# PowerRouting.net
KiCad netlist of a schematic drawn in Altium Designer
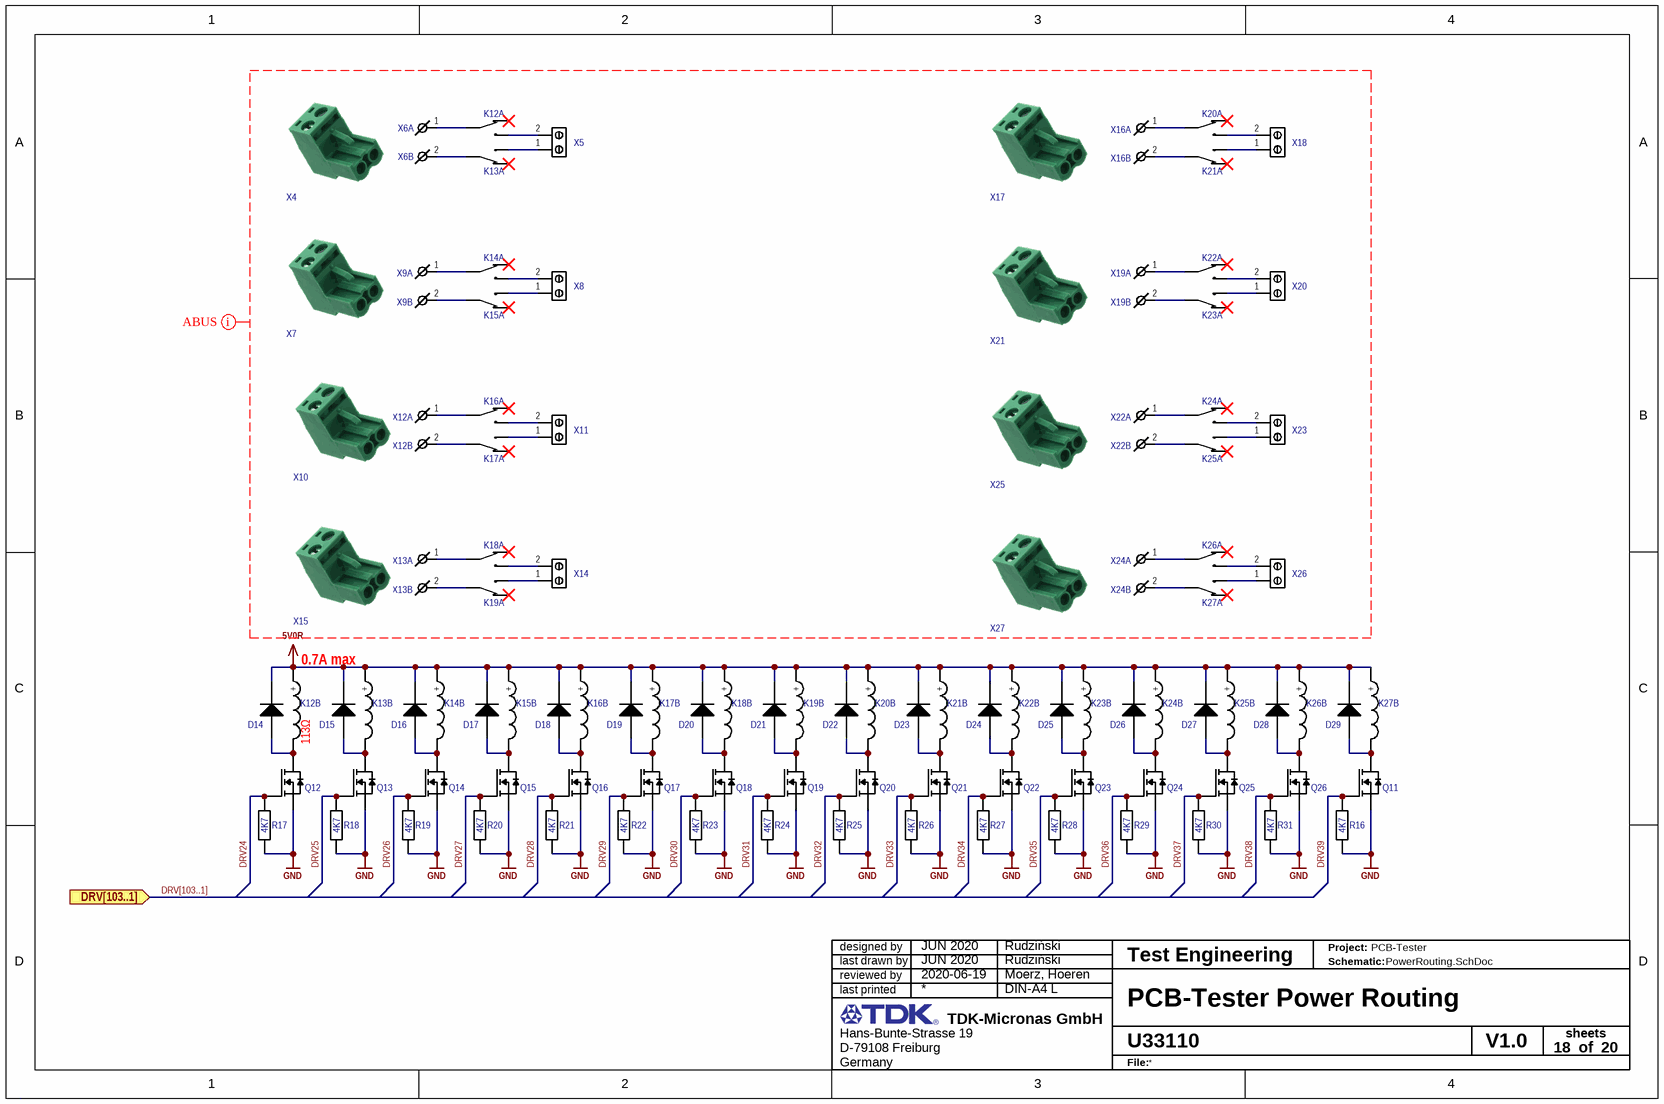
[diagram p0: PowerRouting.SchDoc]

(export (version "E")
  (design (tool "Eeschema 10.0.6"))
  (components
    (comp (ref "D14")
      (value "D")
      (footprint "SOD123")
      (description "DIODE GEN PURP 100V 300MA SOD123")
      (fields
        (field (name "02. DISTRIBUTOR PART NUMBER") "1N4148W-FDICT-ND")
        (field (name "07. MANUFACTURER  PART NUMBER") "1N4148W-7-F")
      )
      (libsource (lib "PCB-Tester-Board-V1") (part "1N4148W"))
    )
    (comp (ref "D15")
      (value "D")
      (footprint "SOD123")
      (description "DIODE GEN PURP 100V 300MA SOD123")
      (fields
        (field (name "02. DISTRIBUTOR PART NUMBER") "1N4148W-FDICT-ND")
        (field (name "07. MANUFACTURER  PART NUMBER") "1N4148W-7-F")
      )
      (libsource (lib "PCB-Tester-Board-V1") (part "1N4148W"))
    )
    (comp (ref "D16")
      (value "D")
      (footprint "SOD123")
      (description "DIODE GEN PURP 100V 300MA SOD123")
      (fields
        (field (name "02. DISTRIBUTOR PART NUMBER") "1N4148W-FDICT-ND")
        (field (name "07. MANUFACTURER  PART NUMBER") "1N4148W-7-F")
      )
      (libsource (lib "PCB-Tester-Board-V1") (part "1N4148W"))
    )
    (comp (ref "D17")
      (value "D")
      (footprint "SOD123")
      (description "DIODE GEN PURP 100V 300MA SOD123")
      (fields
        (field (name "02. DISTRIBUTOR PART NUMBER") "1N4148W-FDICT-ND")
        (field (name "07. MANUFACTURER  PART NUMBER") "1N4148W-7-F")
      )
      (libsource (lib "PCB-Tester-Board-V1") (part "1N4148W"))
    )
    (comp (ref "D18")
      (value "D")
      (footprint "SOD123")
      (description "DIODE GEN PURP 100V 300MA SOD123")
      (fields
        (field (name "02. DISTRIBUTOR PART NUMBER") "1N4148W-FDICT-ND")
        (field (name "07. MANUFACTURER  PART NUMBER") "1N4148W-7-F")
      )
      (libsource (lib "PCB-Tester-Board-V1") (part "1N4148W"))
    )
    (comp (ref "D19")
      (value "D")
      (footprint "SOD123")
      (description "DIODE GEN PURP 100V 300MA SOD123")
      (fields
        (field (name "02. DISTRIBUTOR PART NUMBER") "1N4148W-FDICT-ND")
        (field (name "07. MANUFACTURER  PART NUMBER") "1N4148W-7-F")
      )
      (libsource (lib "PCB-Tester-Board-V1") (part "1N4148W"))
    )
    (comp (ref "D20")
      (value "D")
      (footprint "SOD123")
      (description "DIODE GEN PURP 100V 300MA SOD123")
      (fields
        (field (name "02. DISTRIBUTOR PART NUMBER") "1N4148W-FDICT-ND")
        (field (name "07. MANUFACTURER  PART NUMBER") "1N4148W-7-F")
      )
      (libsource (lib "PCB-Tester-Board-V1") (part "1N4148W"))
    )
    (comp (ref "D21")
      (value "D")
      (footprint "SOD123")
      (description "DIODE GEN PURP 100V 300MA SOD123")
      (fields
        (field (name "02. DISTRIBUTOR PART NUMBER") "1N4148W-FDICT-ND")
        (field (name "07. MANUFACTURER  PART NUMBER") "1N4148W-7-F")
      )
      (libsource (lib "PCB-Tester-Board-V1") (part "1N4148W"))
    )
    (comp (ref "D22")
      (value "D")
      (footprint "SOD123")
      (description "DIODE GEN PURP 100V 300MA SOD123")
      (fields
        (field (name "02. DISTRIBUTOR PART NUMBER") "1N4148W-FDICT-ND")
        (field (name "07. MANUFACTURER  PART NUMBER") "1N4148W-7-F")
      )
      (libsource (lib "PCB-Tester-Board-V1") (part "1N4148W"))
    )
    (comp (ref "D23")
      (value "D")
      (footprint "SOD123")
      (description "DIODE GEN PURP 100V 300MA SOD123")
      (fields
        (field (name "02. DISTRIBUTOR PART NUMBER") "1N4148W-FDICT-ND")
        (field (name "07. MANUFACTURER  PART NUMBER") "1N4148W-7-F")
      )
      (libsource (lib "PCB-Tester-Board-V1") (part "1N4148W"))
    )
    (comp (ref "D24")
      (value "D")
      (footprint "SOD123")
      (description "DIODE GEN PURP 100V 300MA SOD123")
      (fields
        (field (name "02. DISTRIBUTOR PART NUMBER") "1N4148W-FDICT-ND")
        (field (name "07. MANUFACTURER  PART NUMBER") "1N4148W-7-F")
      )
      (libsource (lib "PCB-Tester-Board-V1") (part "1N4148W"))
    )
    (comp (ref "D25")
      (value "D")
      (footprint "SOD123")
      (description "DIODE GEN PURP 100V 300MA SOD123")
      (fields
        (field (name "02. DISTRIBUTOR PART NUMBER") "1N4148W-FDICT-ND")
        (field (name "07. MANUFACTURER  PART NUMBER") "1N4148W-7-F")
      )
      (libsource (lib "PCB-Tester-Board-V1") (part "1N4148W"))
    )
    (comp (ref "D26")
      (value "D")
      (footprint "SOD123")
      (description "DIODE GEN PURP 100V 300MA SOD123")
      (fields
        (field (name "02. DISTRIBUTOR PART NUMBER") "1N4148W-FDICT-ND")
        (field (name "07. MANUFACTURER  PART NUMBER") "1N4148W-7-F")
      )
      (libsource (lib "PCB-Tester-Board-V1") (part "1N4148W"))
    )
    (comp (ref "D27")
      (value "D")
      (footprint "SOD123")
      (description "DIODE GEN PURP 100V 300MA SOD123")
      (fields
        (field (name "02. DISTRIBUTOR PART NUMBER") "1N4148W-FDICT-ND")
        (field (name "07. MANUFACTURER  PART NUMBER") "1N4148W-7-F")
      )
      (libsource (lib "PCB-Tester-Board-V1") (part "1N4148W"))
    )
    (comp (ref "D28")
      (value "D")
      (footprint "SOD123")
      (description "DIODE GEN PURP 100V 300MA SOD123")
      (fields
        (field (name "02. DISTRIBUTOR PART NUMBER") "1N4148W-FDICT-ND")
        (field (name "07. MANUFACTURER  PART NUMBER") "1N4148W-7-F")
      )
      (libsource (lib "PCB-Tester-Board-V1") (part "1N4148W"))
    )
    (comp (ref "D29")
      (value "D")
      (footprint "SOD123")
      (description "DIODE GEN PURP 100V 300MA SOD123")
      (fields
        (field (name "02. DISTRIBUTOR PART NUMBER") "1N4148W-FDICT-ND")
        (field (name "07. MANUFACTURER  PART NUMBER") "1N4148W-7-F")
      )
      (libsource (lib "PCB-Tester-Board-V1") (part "1N4148W"))
    )
    (comp (ref "K12")
      (value "K")
      (footprint "HF118F005-1ZS1")
      (description "5V Power Relay, switch over")
      (fields
        (field (name "02. DISTRIBUTOR PART NUMBER") "176-2821")
        (field (name "07. MANUFACTURER  PART NUMBER") "HF118F/005-1ZS1T(136)")
        (field (name "COIL RESISTANCE") "113Ω")
        (field (name "13. CREATED DATE/NAME") "AUG2018/Hören")
      )
      (libsource (lib "chickenfood") (part "HF118F005-1ZS1"))
    )
    (comp (ref "K13")
      (value "K")
      (footprint "HF118F005-1ZS1")
      (description "5V Power Relay, switch over")
      (fields
        (field (name "02. DISTRIBUTOR PART NUMBER") "176-2821")
        (field (name "07. MANUFACTURER  PART NUMBER") "HF118F/005-1ZS1T(136)")
        (field (name "13. CREATED DATE/NAME") "AUG2018/Hören")
      )
      (libsource (lib "chickenfood") (part "HF118F005-1ZS1"))
    )
    (comp (ref "K14")
      (value "K")
      (footprint "HF118F005-1ZS1")
      (description "5V Power Relay, switch over")
      (fields
        (field (name "02. DISTRIBUTOR PART NUMBER") "176-2821")
        (field (name "07. MANUFACTURER  PART NUMBER") "HF118F/005-1ZS1T(136)")
        (field (name "13. CREATED DATE/NAME") "AUG2018/Hören")
      )
      (libsource (lib "chickenfood") (part "HF118F005-1ZS1"))
    )
    (comp (ref "K15")
      (value "K")
      (footprint "HF118F005-1ZS1")
      (description "5V Power Relay, switch over")
      (fields
        (field (name "02. DISTRIBUTOR PART NUMBER") "176-2821")
        (field (name "07. MANUFACTURER  PART NUMBER") "HF118F/005-1ZS1T(136)")
        (field (name "13. CREATED DATE/NAME") "AUG2018/Hören")
      )
      (libsource (lib "chickenfood") (part "HF118F005-1ZS1"))
    )
    (comp (ref "K16")
      (value "K")
      (footprint "HF118F005-1ZS1")
      (description "5V Power Relay, switch over")
      (fields
        (field (name "02. DISTRIBUTOR PART NUMBER") "176-2821")
        (field (name "07. MANUFACTURER  PART NUMBER") "HF118F/005-1ZS1T(136)")
        (field (name "13. CREATED DATE/NAME") "AUG2018/Hören")
      )
      (libsource (lib "chickenfood") (part "HF118F005-1ZS1"))
    )
    (comp (ref "K17")
      (value "K")
      (footprint "HF118F005-1ZS1")
      (description "5V Power Relay, switch over")
      (fields
        (field (name "02. DISTRIBUTOR PART NUMBER") "176-2821")
        (field (name "07. MANUFACTURER  PART NUMBER") "HF118F/005-1ZS1T(136)")
        (field (name "13. CREATED DATE/NAME") "AUG2018/Hören")
      )
      (libsource (lib "") (part "HF118F005-1ZS1_1"))
    )
    (comp (ref "K18")
      (value "K")
      (footprint "HF118F005-1ZS1")
      (description "5V Power Relay, switch over")
      (fields
        (field (name "02. DISTRIBUTOR PART NUMBER") "176-2821")
        (field (name "07. MANUFACTURER  PART NUMBER") "HF118F/005-1ZS1T(136)")
        (field (name "13. CREATED DATE/NAME") "AUG2018/Hören")
      )
      (libsource (lib "chickenfood") (part "HF118F005-1ZS1"))
    )
    (comp (ref "K19")
      (value "K")
      (footprint "HF118F005-1ZS1")
      (description "5V Power Relay, switch over")
      (fields
        (field (name "02. DISTRIBUTOR PART NUMBER") "176-2821")
        (field (name "07. MANUFACTURER  PART NUMBER") "HF118F/005-1ZS1T(136)")
        (field (name "13. CREATED DATE/NAME") "AUG2018/Hören")
      )
      (libsource (lib "") (part "HF118F005-1ZS1_1"))
    )
    (comp (ref "K20")
      (value "K")
      (footprint "HF118F005-1ZS1")
      (description "5V Power Relay, switch over")
      (fields
        (field (name "02. DISTRIBUTOR PART NUMBER") "176-2821")
        (field (name "07. MANUFACTURER  PART NUMBER") "HF118F/005-1ZS1T(136)")
        (field (name "13. CREATED DATE/NAME") "AUG2018/Hören")
      )
      (libsource (lib "chickenfood") (part "HF118F005-1ZS1"))
    )
    (comp (ref "K21")
      (value "K")
      (footprint "HF118F005-1ZS1")
      (description "5V Power Relay, switch over")
      (fields
        (field (name "02. DISTRIBUTOR PART NUMBER") "176-2821")
        (field (name "07. MANUFACTURER  PART NUMBER") "HF118F/005-1ZS1T(136)")
        (field (name "13. CREATED DATE/NAME") "AUG2018/Hören")
      )
      (libsource (lib "chickenfood") (part "HF118F005-1ZS1"))
    )
    (comp (ref "K22")
      (value "K")
      (footprint "HF118F005-1ZS1")
      (description "5V Power Relay, switch over")
      (fields
        (field (name "02. DISTRIBUTOR PART NUMBER") "176-2821")
        (field (name "07. MANUFACTURER  PART NUMBER") "HF118F/005-1ZS1T(136)")
        (field (name "13. CREATED DATE/NAME") "AUG2018/Hören")
      )
      (libsource (lib "chickenfood") (part "HF118F005-1ZS1"))
    )
    (comp (ref "K23")
      (value "K")
      (footprint "HF118F005-1ZS1")
      (description "5V Power Relay, switch over")
      (fields
        (field (name "02. DISTRIBUTOR PART NUMBER") "176-2821")
        (field (name "07. MANUFACTURER  PART NUMBER") "HF118F/005-1ZS1T(136)")
        (field (name "13. CREATED DATE/NAME") "AUG2018/Hören")
      )
      (libsource (lib "") (part "HF118F005-1ZS1_1"))
    )
    (comp (ref "K24")
      (value "K")
      (footprint "HF118F005-1ZS1")
      (description "5V Power Relay, switch over")
      (fields
        (field (name "02. DISTRIBUTOR PART NUMBER") "176-2821")
        (field (name "07. MANUFACTURER  PART NUMBER") "HF118F/005-1ZS1T(136)")
        (field (name "13. CREATED DATE/NAME") "AUG2018/Hören")
      )
      (libsource (lib "chickenfood") (part "HF118F005-1ZS1"))
    )
    (comp (ref "K25")
      (value "K")
      (footprint "HF118F005-1ZS1")
      (description "5V Power Relay, switch over")
      (fields
        (field (name "02. DISTRIBUTOR PART NUMBER") "176-2821")
        (field (name "07. MANUFACTURER  PART NUMBER") "HF118F/005-1ZS1T(136)")
        (field (name "13. CREATED DATE/NAME") "AUG2018/Hören")
      )
      (libsource (lib "") (part "HF118F005-1ZS1_1"))
    )
    (comp (ref "K26")
      (value "K")
      (footprint "HF118F005-1ZS1")
      (description "5V Power Relay, switch over")
      (fields
        (field (name "02. DISTRIBUTOR PART NUMBER") "176-2821")
        (field (name "07. MANUFACTURER  PART NUMBER") "HF118F/005-1ZS1T(136)")
        (field (name "13. CREATED DATE/NAME") "AUG2018/Hören")
      )
      (libsource (lib "chickenfood") (part "HF118F005-1ZS1"))
    )
    (comp (ref "K27")
      (value "K")
      (footprint "HF118F005-1ZS1")
      (description "5V Power Relay, switch over")
      (fields
        (field (name "02. DISTRIBUTOR PART NUMBER") "176-2821")
        (field (name "07. MANUFACTURER  PART NUMBER") "HF118F/005-1ZS1T(136)")
        (field (name "13. CREATED DATE/NAME") "AUG2018/Hören")
      )
      (libsource (lib "") (part "HF118F005-1ZS1_1"))
    )
    (comp (ref "Q11")
      (value "Q")
      (footprint "SOT23-3")
      (description "MOSFET N-CH 25V 680MA SOT-23")
      (fields
        (field (name "02. DISTRIBUTOR PART NUMBER") "FDV303NDKR-ND")
        (field (name "07. MANUFACTURER  PART NUMBER") "FDV303N")
        (field (name "13. CREATED DATE/NAME") "AUG 2018 / Hören")
      )
      (libsource (lib "SCT8-Board1") (part "FDV303N"))
    )
    (comp (ref "Q12")
      (value "Q")
      (footprint "SOT23-3")
      (description "MOSFET N-CH 25V 680MA SOT-23")
      (fields
        (field (name "02. DISTRIBUTOR PART NUMBER") "FDV303NDKR-ND")
        (field (name "07. MANUFACTURER  PART NUMBER") "FDV303N")
        (field (name "13. CREATED DATE/NAME") "AUG 2018 / Hören")
      )
      (libsource (lib "SCT8-Board1") (part "FDV303N"))
    )
    (comp (ref "Q13")
      (value "Q")
      (footprint "SOT23-3")
      (description "MOSFET N-CH 25V 680MA SOT-23")
      (fields
        (field (name "02. DISTRIBUTOR PART NUMBER") "FDV303NDKR-ND")
        (field (name "07. MANUFACTURER  PART NUMBER") "FDV303N")
        (field (name "13. CREATED DATE/NAME") "AUG 2018 / Hören")
      )
      (libsource (lib "SCT8-Board1") (part "FDV303N"))
    )
    (comp (ref "Q14")
      (value "Q")
      (footprint "SOT23-3")
      (description "MOSFET N-CH 25V 680MA SOT-23")
      (fields
        (field (name "02. DISTRIBUTOR PART NUMBER") "FDV303NDKR-ND")
        (field (name "07. MANUFACTURER  PART NUMBER") "FDV303N")
        (field (name "13. CREATED DATE/NAME") "AUG 2018 / Hören")
      )
      (libsource (lib "SCT8-Board1") (part "FDV303N"))
    )
    (comp (ref "Q15")
      (value "Q")
      (footprint "SOT23-3")
      (description "MOSFET N-CH 25V 680MA SOT-23")
      (fields
        (field (name "02. DISTRIBUTOR PART NUMBER") "FDV303NDKR-ND")
        (field (name "07. MANUFACTURER  PART NUMBER") "FDV303N")
        (field (name "13. CREATED DATE/NAME") "AUG 2018 / Hören")
      )
      (libsource (lib "SCT8-Board1") (part "FDV303N"))
    )
    (comp (ref "Q16")
      (value "Q")
      (footprint "SOT23-3")
      (description "MOSFET N-CH 25V 680MA SOT-23")
      (fields
        (field (name "02. DISTRIBUTOR PART NUMBER") "FDV303NDKR-ND")
        (field (name "07. MANUFACTURER  PART NUMBER") "FDV303N")
        (field (name "13. CREATED DATE/NAME") "AUG 2018 / Hören")
      )
      (libsource (lib "SCT8-Board1") (part "FDV303N"))
    )
    (comp (ref "Q17")
      (value "Q")
      (footprint "SOT23-3")
      (description "MOSFET N-CH 25V 680MA SOT-23")
      (fields
        (field (name "02. DISTRIBUTOR PART NUMBER") "FDV303NDKR-ND")
        (field (name "07. MANUFACTURER  PART NUMBER") "FDV303N")
        (field (name "13. CREATED DATE/NAME") "AUG 2018 / Hören")
      )
      (libsource (lib "SCT8-Board1") (part "FDV303N"))
    )
    (comp (ref "Q18")
      (value "Q")
      (footprint "SOT23-3")
      (description "MOSFET N-CH 25V 680MA SOT-23")
      (fields
        (field (name "02. DISTRIBUTOR PART NUMBER") "FDV303NDKR-ND")
        (field (name "07. MANUFACTURER  PART NUMBER") "FDV303N")
        (field (name "13. CREATED DATE/NAME") "AUG 2018 / Hören")
      )
      (libsource (lib "SCT8-Board1") (part "FDV303N"))
    )
    (comp (ref "Q19")
      (value "Q")
      (footprint "SOT23-3")
      (description "MOSFET N-CH 25V 680MA SOT-23")
      (fields
        (field (name "02. DISTRIBUTOR PART NUMBER") "FDV303NDKR-ND")
        (field (name "07. MANUFACTURER  PART NUMBER") "FDV303N")
        (field (name "13. CREATED DATE/NAME") "AUG 2018 / Hören")
      )
      (libsource (lib "SCT8-Board1") (part "FDV303N"))
    )
    (comp (ref "Q20")
      (value "Q")
      (footprint "SOT23-3")
      (description "MOSFET N-CH 25V 680MA SOT-23")
      (fields
        (field (name "02. DISTRIBUTOR PART NUMBER") "FDV303NDKR-ND")
        (field (name "07. MANUFACTURER  PART NUMBER") "FDV303N")
        (field (name "13. CREATED DATE/NAME") "AUG 2018 / Hören")
      )
      (libsource (lib "SCT8-Board1") (part "FDV303N"))
    )
    (comp (ref "Q21")
      (value "Q")
      (footprint "SOT23-3")
      (description "MOSFET N-CH 25V 680MA SOT-23")
      (fields
        (field (name "02. DISTRIBUTOR PART NUMBER") "FDV303NDKR-ND")
        (field (name "07. MANUFACTURER  PART NUMBER") "FDV303N")
        (field (name "13. CREATED DATE/NAME") "AUG 2018 / Hören")
      )
      (libsource (lib "SCT8-Board1") (part "FDV303N"))
    )
    (comp (ref "Q22")
      (value "Q")
      (footprint "SOT23-3")
      (description "MOSFET N-CH 25V 680MA SOT-23")
      (fields
        (field (name "02. DISTRIBUTOR PART NUMBER") "FDV303NDKR-ND")
        (field (name "07. MANUFACTURER  PART NUMBER") "FDV303N")
        (field (name "13. CREATED DATE/NAME") "AUG 2018 / Hören")
      )
      (libsource (lib "SCT8-Board1") (part "FDV303N"))
    )
    (comp (ref "Q23")
      (value "Q")
      (footprint "SOT23-3")
      (description "MOSFET N-CH 25V 680MA SOT-23")
      (fields
        (field (name "02. DISTRIBUTOR PART NUMBER") "FDV303NDKR-ND")
        (field (name "07. MANUFACTURER  PART NUMBER") "FDV303N")
        (field (name "13. CREATED DATE/NAME") "AUG 2018 / Hören")
      )
      (libsource (lib "SCT8-Board1") (part "FDV303N"))
    )
    (comp (ref "Q24")
      (value "Q")
      (footprint "SOT23-3")
      (description "MOSFET N-CH 25V 680MA SOT-23")
      (fields
        (field (name "02. DISTRIBUTOR PART NUMBER") "FDV303NDKR-ND")
        (field (name "07. MANUFACTURER  PART NUMBER") "FDV303N")
        (field (name "13. CREATED DATE/NAME") "AUG 2018 / Hören")
      )
      (libsource (lib "SCT8-Board1") (part "FDV303N"))
    )
    (comp (ref "Q25")
      (value "Q")
      (footprint "SOT23-3")
      (description "MOSFET N-CH 25V 680MA SOT-23")
      (fields
        (field (name "02. DISTRIBUTOR PART NUMBER") "FDV303NDKR-ND")
        (field (name "07. MANUFACTURER  PART NUMBER") "FDV303N")
        (field (name "13. CREATED DATE/NAME") "AUG 2018 / Hören")
      )
      (libsource (lib "SCT8-Board1") (part "FDV303N"))
    )
    (comp (ref "Q26")
      (value "Q")
      (footprint "SOT23-3")
      (description "MOSFET N-CH 25V 680MA SOT-23")
      (fields
        (field (name "02. DISTRIBUTOR PART NUMBER") "FDV303NDKR-ND")
        (field (name "07. MANUFACTURER  PART NUMBER") "FDV303N")
        (field (name "13. CREATED DATE/NAME") "AUG 2018 / Hören")
      )
      (libsource (lib "SCT8-Board1") (part "FDV303N"))
    )
    (comp (ref "R16")
      (value "4K7")
      (footprint "R0603 Reflow")
      (description "RES SMD 4.7K OHM 1% 1/10W 0603")
      (fields
        (field (name "TOLERANCE") "±1%")
        (field (name "02. DISTRIBUTOR PART NUMBER") "311-4.70KHRCT-ND")
        (field (name "13. CREATED DATE/NAME") "AUG2018/Hören")
      )
      (libsource (lib "chickenfood") (part "R"))
    )
    (comp (ref "R17")
      (value "4K7")
      (footprint "R0603 Reflow")
      (description "RES SMD 4.7K OHM 1% 1/10W 0603")
      (fields
        (field (name "TOLERANCE") "±1%")
        (field (name "02. DISTRIBUTOR PART NUMBER") "311-4.70KHRCT-ND")
        (field (name "13. CREATED DATE/NAME") "AUG2018/Hören")
      )
      (libsource (lib "chickenfood") (part "R"))
    )
    (comp (ref "R18")
      (value "4K7")
      (footprint "R0603 Reflow")
      (description "RES SMD 4.7K OHM 1% 1/10W 0603")
      (fields
        (field (name "TOLERANCE") "±1%")
        (field (name "02. DISTRIBUTOR PART NUMBER") "311-4.70KHRCT-ND")
        (field (name "13. CREATED DATE/NAME") "AUG2018/Hören")
      )
      (libsource (lib "chickenfood") (part "R"))
    )
    (comp (ref "R19")
      (value "4K7")
      (footprint "R0603 Reflow")
      (description "RES SMD 4.7K OHM 1% 1/10W 0603")
      (fields
        (field (name "TOLERANCE") "±1%")
        (field (name "02. DISTRIBUTOR PART NUMBER") "311-4.70KHRCT-ND")
        (field (name "13. CREATED DATE/NAME") "AUG2018/Hören")
      )
      (libsource (lib "chickenfood") (part "R"))
    )
    (comp (ref "R20")
      (value "4K7")
      (footprint "R0603 Reflow")
      (description "RES SMD 4.7K OHM 1% 1/10W 0603")
      (fields
        (field (name "TOLERANCE") "±1%")
        (field (name "02. DISTRIBUTOR PART NUMBER") "311-4.70KHRCT-ND")
        (field (name "13. CREATED DATE/NAME") "AUG2018/Hören")
      )
      (libsource (lib "chickenfood") (part "R"))
    )
    (comp (ref "R21")
      (value "4K7")
      (footprint "R0603 Reflow")
      (description "RES SMD 4.7K OHM 1% 1/10W 0603")
      (fields
        (field (name "TOLERANCE") "±1%")
        (field (name "02. DISTRIBUTOR PART NUMBER") "311-4.70KHRCT-ND")
        (field (name "13. CREATED DATE/NAME") "AUG2018/Hören")
      )
      (libsource (lib "chickenfood") (part "R"))
    )
    (comp (ref "R22")
      (value "4K7")
      (footprint "R0603 Reflow")
      (description "RES SMD 4.7K OHM 1% 1/10W 0603")
      (fields
        (field (name "TOLERANCE") "±1%")
        (field (name "02. DISTRIBUTOR PART NUMBER") "311-4.70KHRCT-ND")
        (field (name "13. CREATED DATE/NAME") "AUG2018/Hören")
      )
      (libsource (lib "chickenfood") (part "R"))
    )
    (comp (ref "R23")
      (value "4K7")
      (footprint "R0603 Reflow")
      (description "RES SMD 4.7K OHM 1% 1/10W 0603")
      (fields
        (field (name "TOLERANCE") "±1%")
        (field (name "02. DISTRIBUTOR PART NUMBER") "311-4.70KHRCT-ND")
        (field (name "13. CREATED DATE/NAME") "AUG2018/Hören")
      )
      (libsource (lib "chickenfood") (part "R"))
    )
    (comp (ref "R24")
      (value "4K7")
      (footprint "R0603 Reflow")
      (description "RES SMD 4.7K OHM 1% 1/10W 0603")
      (fields
        (field (name "TOLERANCE") "±1%")
        (field (name "02. DISTRIBUTOR PART NUMBER") "311-4.70KHRCT-ND")
        (field (name "13. CREATED DATE/NAME") "AUG2018/Hören")
      )
      (libsource (lib "chickenfood") (part "R"))
    )
    (comp (ref "R25")
      (value "4K7")
      (footprint "R0603 Reflow")
      (description "RES SMD 4.7K OHM 1% 1/10W 0603")
      (fields
        (field (name "TOLERANCE") "±1%")
        (field (name "02. DISTRIBUTOR PART NUMBER") "311-4.70KHRCT-ND")
        (field (name "13. CREATED DATE/NAME") "AUG2018/Hören")
      )
      (libsource (lib "chickenfood") (part "R"))
    )
    (comp (ref "R26")
      (value "4K7")
      (footprint "R0603 Reflow")
      (description "RES SMD 4.7K OHM 1% 1/10W 0603")
      (fields
        (field (name "TOLERANCE") "±1%")
        (field (name "02. DISTRIBUTOR PART NUMBER") "311-4.70KHRCT-ND")
        (field (name "13. CREATED DATE/NAME") "AUG2018/Hören")
      )
      (libsource (lib "chickenfood") (part "R"))
    )
    (comp (ref "R27")
      (value "4K7")
      (footprint "R0603 Reflow")
      (description "RES SMD 4.7K OHM 1% 1/10W 0603")
      (fields
        (field (name "TOLERANCE") "±1%")
        (field (name "02. DISTRIBUTOR PART NUMBER") "311-4.70KHRCT-ND")
        (field (name "13. CREATED DATE/NAME") "AUG2018/Hören")
      )
      (libsource (lib "chickenfood") (part "R"))
    )
    (comp (ref "R28")
      (value "4K7")
      (footprint "R0603 Reflow")
      (description "RES SMD 4.7K OHM 1% 1/10W 0603")
      (fields
        (field (name "TOLERANCE") "±1%")
        (field (name "02. DISTRIBUTOR PART NUMBER") "311-4.70KHRCT-ND")
        (field (name "13. CREATED DATE/NAME") "AUG2018/Hören")
      )
      (libsource (lib "chickenfood") (part "R"))
    )
    (comp (ref "R29")
      (value "4K7")
      (footprint "R0603 Reflow")
      (description "RES SMD 4.7K OHM 1% 1/10W 0603")
      (fields
        (field (name "TOLERANCE") "±1%")
        (field (name "02. DISTRIBUTOR PART NUMBER") "311-4.70KHRCT-ND")
        (field (name "13. CREATED DATE/NAME") "AUG2018/Hören")
      )
      (libsource (lib "chickenfood") (part "R"))
    )
    (comp (ref "R30")
      (value "4K7")
      (footprint "R0603 Reflow")
      (description "RES SMD 4.7K OHM 1% 1/10W 0603")
      (fields
        (field (name "TOLERANCE") "±1%")
        (field (name "02. DISTRIBUTOR PART NUMBER") "311-4.70KHRCT-ND")
        (field (name "13. CREATED DATE/NAME") "AUG2018/Hören")
      )
      (libsource (lib "chickenfood") (part "R"))
    )
    (comp (ref "R31")
      (value "4K7")
      (footprint "R0603 Reflow")
      (description "RES SMD 4.7K OHM 1% 1/10W 0603")
      (fields
        (field (name "TOLERANCE") "±1%")
        (field (name "02. DISTRIBUTOR PART NUMBER") "311-4.70KHRCT-ND")
        (field (name "13. CREATED DATE/NAME") "AUG2018/Hören")
      )
      (libsource (lib "chickenfood") (part "R"))
    )
    (comp (ref "X4")
      (value "X")
      (footprint "691352710002")
      (description "TERM BLOCK PLUG 2POS STR 5MM")
      (fields
        (field (name "02. DISTRIBUTOR PART NUMBER") "732-2775-ND")
        (field (name "07. MANUFACTURER  PART NUMBER") "691352710002")
        (field (name "13. CREATED DATE/NAME") "??? / Hören")
      )
      (libsource (lib "PCB-Tester-Board-V1") (part "691352710002"))
    )
    (comp (ref "X5")
      (value "X")
      (footprint "1731721")
      (description "TERM BLK 2P SIDE ENT 7.62MM PCB")
      (fields
        (field (name "02. DISTRIBUTOR PART NUMBER") "277-5849-ND")
        (field (name "07. MANUFACTURER  PART NUMBER") "1731721")
        (field (name "13. CREATED DATE/NAME") "JAN 2019 / Hören")
      )
      (libsource (lib "Connectors") (part "1731721"))
    )
    (comp (ref "X6")
      (value "X")
      (footprint "691312710002")
      (description "TERM BLOCK HDR 2POS 90DEG 5MM")
      (fields
        (field (name "02. DISTRIBUTOR PART NUMBER") "732-2805-ND")
        (field (name "07. MANUFACTURER  PART NUMBER") "691312710002")
        (field (name "13. CREATED DATE/NAME") "??? / Hören")
      )
      (libsource (lib "Connectors") (part "691312710002"))
    )
    (comp (ref "X7")
      (value "X")
      (footprint "691352710002")
      (description "TERM BLOCK PLUG 2POS STR 5MM")
      (fields
        (field (name "02. DISTRIBUTOR PART NUMBER") "732-2775-ND")
        (field (name "07. MANUFACTURER  PART NUMBER") "691352710002")
        (field (name "13. CREATED DATE/NAME") "??? / Hören")
      )
      (libsource (lib "PCB-Tester-Board-V1") (part "691352710002"))
    )
    (comp (ref "X8")
      (value "X")
      (footprint "1731721")
      (description "TERM BLK 2P SIDE ENT 7.62MM PCB")
      (fields
        (field (name "02. DISTRIBUTOR PART NUMBER") "277-5849-ND")
        (field (name "07. MANUFACTURER  PART NUMBER") "1731721")
        (field (name "13. CREATED DATE/NAME") "JAN 2019 / Hören")
      )
      (libsource (lib "Connectors") (part "1731721"))
    )
    (comp (ref "X9")
      (value "X")
      (footprint "691312710002")
      (description "TERM BLOCK HDR 2POS 90DEG 5MM")
      (fields
        (field (name "02. DISTRIBUTOR PART NUMBER") "732-2805-ND")
        (field (name "07. MANUFACTURER  PART NUMBER") "691312710002")
        (field (name "13. CREATED DATE/NAME") "??? / Hören")
      )
      (libsource (lib "Connectors") (part "691312710002"))
    )
    (comp (ref "X10")
      (value "X")
      (footprint "691352710002")
      (description "TERM BLOCK PLUG 2POS STR 5MM")
      (fields
        (field (name "02. DISTRIBUTOR PART NUMBER") "732-2775-ND")
        (field (name "07. MANUFACTURER  PART NUMBER") "691352710002")
        (field (name "13. CREATED DATE/NAME") "??? / Hören")
      )
      (libsource (lib "PCB-Tester-Board-V1") (part "691352710002"))
    )
    (comp (ref "X11")
      (value "X")
      (footprint "1731721")
      (description "TERM BLK 2P SIDE ENT 7.62MM PCB")
      (fields
        (field (name "02. DISTRIBUTOR PART NUMBER") "277-5849-ND")
        (field (name "07. MANUFACTURER  PART NUMBER") "1731721")
        (field (name "13. CREATED DATE/NAME") "JAN 2019 / Hören")
      )
      (libsource (lib "Connectors") (part "1731721"))
    )
    (comp (ref "X12")
      (value "X")
      (footprint "691312710002")
      (description "TERM BLOCK HDR 2POS 90DEG 5MM")
      (fields
        (field (name "02. DISTRIBUTOR PART NUMBER") "732-2805-ND")
        (field (name "07. MANUFACTURER  PART NUMBER") "691312710002")
        (field (name "13. CREATED DATE/NAME") "??? / Hören")
      )
      (libsource (lib "Connectors") (part "691312710002"))
    )
    (comp (ref "X13")
      (value "X")
      (footprint "691312710002")
      (description "TERM BLOCK HDR 2POS 90DEG 5MM")
      (fields
        (field (name "02. DISTRIBUTOR PART NUMBER") "732-2805-ND")
        (field (name "07. MANUFACTURER  PART NUMBER") "691312710002")
        (field (name "13. CREATED DATE/NAME") "??? / Hören")
      )
      (libsource (lib "Connectors") (part "691312710002"))
    )
    (comp (ref "X14")
      (value "X")
      (footprint "1731721")
      (description "TERM BLK 2P SIDE ENT 7.62MM PCB")
      (fields
        (field (name "02. DISTRIBUTOR PART NUMBER") "277-5849-ND")
        (field (name "07. MANUFACTURER  PART NUMBER") "1731721")
        (field (name "13. CREATED DATE/NAME") "JAN 2019 / Hören")
      )
      (libsource (lib "Connectors") (part "1731721"))
    )
    (comp (ref "X15")
      (value "X")
      (footprint "691352710002")
      (description "TERM BLOCK PLUG 2POS STR 5MM")
      (fields
        (field (name "02. DISTRIBUTOR PART NUMBER") "732-2775-ND")
        (field (name "07. MANUFACTURER  PART NUMBER") "691352710002")
        (field (name "13. CREATED DATE/NAME") "??? / Hören")
      )
      (libsource (lib "PCB-Tester-Board-V1") (part "691352710002"))
    )
    (comp (ref "X16")
      (value "X")
      (footprint "691312710002")
      (description "TERM BLOCK HDR 2POS 90DEG 5MM")
      (fields
        (field (name "02. DISTRIBUTOR PART NUMBER") "732-2805-ND")
        (field (name "07. MANUFACTURER  PART NUMBER") "691312710002")
        (field (name "13. CREATED DATE/NAME") "??? / Hören")
      )
      (libsource (lib "Connectors") (part "691312710002"))
    )
    (comp (ref "X17")
      (value "X")
      (footprint "691352710002")
      (description "TERM BLOCK PLUG 2POS STR 5MM")
      (fields
        (field (name "02. DISTRIBUTOR PART NUMBER") "732-2775-ND")
        (field (name "07. MANUFACTURER  PART NUMBER") "691352710002")
        (field (name "13. CREATED DATE/NAME") "??? / Hören")
      )
      (libsource (lib "PCB-Tester-Board-V1") (part "691352710002"))
    )
    (comp (ref "X18")
      (value "X")
      (footprint "1731721")
      (description "TERM BLK 2P SIDE ENT 7.62MM PCB")
      (fields
        (field (name "02. DISTRIBUTOR PART NUMBER") "277-5849-ND")
        (field (name "07. MANUFACTURER  PART NUMBER") "1731721")
        (field (name "13. CREATED DATE/NAME") "JAN 2019 / Hören")
      )
      (libsource (lib "Connectors") (part "1731721"))
    )
    (comp (ref "X19")
      (value "X")
      (footprint "691312710002")
      (description "TERM BLOCK HDR 2POS 90DEG 5MM")
      (fields
        (field (name "02. DISTRIBUTOR PART NUMBER") "732-2805-ND")
        (field (name "07. MANUFACTURER  PART NUMBER") "691312710002")
        (field (name "13. CREATED DATE/NAME") "??? / Hören")
      )
      (libsource (lib "Connectors") (part "691312710002"))
    )
    (comp (ref "X20")
      (value "X")
      (footprint "1731721")
      (description "TERM BLK 2P SIDE ENT 7.62MM PCB")
      (fields
        (field (name "02. DISTRIBUTOR PART NUMBER") "277-5849-ND")
        (field (name "07. MANUFACTURER  PART NUMBER") "1731721")
        (field (name "13. CREATED DATE/NAME") "JAN 2019 / Hören")
      )
      (libsource (lib "Connectors") (part "1731721"))
    )
    (comp (ref "X21")
      (value "X")
      (footprint "691352710002")
      (description "TERM BLOCK PLUG 2POS STR 5MM")
      (fields
        (field (name "02. DISTRIBUTOR PART NUMBER") "732-2775-ND")
        (field (name "07. MANUFACTURER  PART NUMBER") "691352710002")
        (field (name "13. CREATED DATE/NAME") "??? / Hören")
      )
      (libsource (lib "PCB-Tester-Board-V1") (part "691352710002"))
    )
    (comp (ref "X22")
      (value "X")
      (footprint "691312710002")
      (description "TERM BLOCK HDR 2POS 90DEG 5MM")
      (fields
        (field (name "02. DISTRIBUTOR PART NUMBER") "732-2805-ND")
        (field (name "07. MANUFACTURER  PART NUMBER") "691312710002")
        (field (name "13. CREATED DATE/NAME") "??? / Hören")
      )
      (libsource (lib "Connectors") (part "691312710002"))
    )
    (comp (ref "X23")
      (value "X")
      (footprint "1731721")
      (description "TERM BLK 2P SIDE ENT 7.62MM PCB")
      (fields
        (field (name "02. DISTRIBUTOR PART NUMBER") "277-5849-ND")
        (field (name "07. MANUFACTURER  PART NUMBER") "1731721")
        (field (name "13. CREATED DATE/NAME") "JAN 2019 / Hören")
      )
      (libsource (lib "Connectors") (part "1731721"))
    )
    (comp (ref "X24")
      (value "X")
      (footprint "691312710002")
      (description "TERM BLOCK HDR 2POS 90DEG 5MM")
      (fields
        (field (name "02. DISTRIBUTOR PART NUMBER") "732-2805-ND")
        (field (name "07. MANUFACTURER  PART NUMBER") "691312710002")
        (field (name "13. CREATED DATE/NAME") "??? / Hören")
      )
      (libsource (lib "Connectors") (part "691312710002"))
    )
    (comp (ref "X25")
      (value "X")
      (footprint "691352710002")
      (description "TERM BLOCK PLUG 2POS STR 5MM")
      (fields
        (field (name "02. DISTRIBUTOR PART NUMBER") "732-2775-ND")
        (field (name "07. MANUFACTURER  PART NUMBER") "691352710002")
        (field (name "13. CREATED DATE/NAME") "??? / Hören")
      )
      (libsource (lib "PCB-Tester-Board-V1") (part "691352710002"))
    )
    (comp (ref "X26")
      (value "X")
      (footprint "1731721")
      (description "TERM BLK 2P SIDE ENT 7.62MM PCB")
      (fields
        (field (name "02. DISTRIBUTOR PART NUMBER") "277-5849-ND")
        (field (name "07. MANUFACTURER  PART NUMBER") "1731721")
        (field (name "13. CREATED DATE/NAME") "JAN 2019 / Hören")
      )
      (libsource (lib "Connectors") (part "1731721"))
    )
    (comp (ref "X27")
      (value "X")
      (footprint "691352710002")
      (description "TERM BLOCK PLUG 2POS STR 5MM")
      (fields
        (field (name "02. DISTRIBUTOR PART NUMBER") "732-2775-ND")
        (field (name "07. MANUFACTURER  PART NUMBER") "691352710002")
        (field (name "13. CREATED DATE/NAME") "??? / Hören")
      )
      (libsource (lib "PCB-Tester-Board-V1") (part "691352710002"))
    )
  )
  (nets
    (net (code "88") (name "/DRV24") (class "Default")
      (node (ref "Q12") (pin "1") (pinfunction "G_1") (pintype "passive"))
      (node (ref "R17") (pin "2") (pinfunction "2_2") (pintype "passive"))
    )
    (net (code "89") (name "/DRV25") (class "Default")
      (node (ref "Q13") (pin "1") (pinfunction "G_1") (pintype "passive"))
      (node (ref "R18") (pin "2") (pinfunction "2_2") (pintype "passive"))
    )
    (net (code "90") (name "/DRV26") (class "Default")
      (node (ref "Q14") (pin "1") (pinfunction "G_1") (pintype "passive"))
      (node (ref "R19") (pin "2") (pinfunction "2_2") (pintype "passive"))
    )
    (net (code "91") (name "/DRV27") (class "Default")
      (node (ref "Q15") (pin "1") (pinfunction "G_1") (pintype "passive"))
      (node (ref "R20") (pin "2") (pinfunction "2_2") (pintype "passive"))
    )
    (net (code "92") (name "/DRV28") (class "Default")
      (node (ref "Q16") (pin "1") (pinfunction "G_1") (pintype "passive"))
      (node (ref "R21") (pin "2") (pinfunction "2_2") (pintype "passive"))
    )
    (net (code "93") (name "/DRV29") (class "Default")
      (node (ref "Q17") (pin "1") (pinfunction "G_1") (pintype "passive"))
      (node (ref "R22") (pin "2") (pinfunction "2_2") (pintype "passive"))
    )
    (net (code "94") (name "/DRV30") (class "Default")
      (node (ref "Q18") (pin "1") (pinfunction "G_1") (pintype "passive"))
      (node (ref "R23") (pin "2") (pinfunction "2_2") (pintype "passive"))
    )
    (net (code "95") (name "/DRV31") (class "Default")
      (node (ref "Q19") (pin "1") (pinfunction "G_1") (pintype "passive"))
      (node (ref "R24") (pin "2") (pinfunction "2_2") (pintype "passive"))
    )
    (net (code "96") (name "/DRV32") (class "Default")
      (node (ref "Q20") (pin "1") (pinfunction "G_1") (pintype "passive"))
      (node (ref "R25") (pin "2") (pinfunction "2_2") (pintype "passive"))
    )
    (net (code "97") (name "/DRV33") (class "Default")
      (node (ref "Q21") (pin "1") (pinfunction "G_1") (pintype "passive"))
      (node (ref "R26") (pin "2") (pinfunction "2_2") (pintype "passive"))
    )
    (net (code "98") (name "/DRV34") (class "Default")
      (node (ref "Q22") (pin "1") (pinfunction "G_1") (pintype "passive"))
      (node (ref "R27") (pin "2") (pinfunction "2_2") (pintype "passive"))
    )
    (net (code "99") (name "/DRV35") (class "Default")
      (node (ref "Q23") (pin "1") (pinfunction "G_1") (pintype "passive"))
      (node (ref "R28") (pin "2") (pinfunction "2_2") (pintype "passive"))
    )
    (net (code "100") (name "/DRV36") (class "Default")
      (node (ref "Q24") (pin "1") (pinfunction "G_1") (pintype "passive"))
      (node (ref "R29") (pin "2") (pinfunction "2_2") (pintype "passive"))
    )
    (net (code "101") (name "/DRV37") (class "Default")
      (node (ref "Q25") (pin "1") (pinfunction "G_1") (pintype "passive"))
      (node (ref "R30") (pin "2") (pinfunction "2_2") (pintype "passive"))
    )
    (net (code "102") (name "/DRV38") (class "Default")
      (node (ref "Q26") (pin "1") (pinfunction "G_1") (pintype "passive"))
      (node (ref "R31") (pin "2") (pinfunction "2_2") (pintype "passive"))
    )
    (net (code "103") (name "/DRV39") (class "Default")
      (node (ref "Q11") (pin "1") (pinfunction "G_1") (pintype "passive"))
      (node (ref "R16") (pin "2") (pinfunction "2_2") (pintype "passive"))
    )
    (net (code "105") (name "5V0R") (class "Default")
      (node (ref "D14") (pin "2") (pinfunction "C_2") (pintype "passive"))
      (node (ref "D15") (pin "2") (pinfunction "C_2") (pintype "passive"))
      (node (ref "D16") (pin "2") (pinfunction "C_2") (pintype "passive"))
      (node (ref "D17") (pin "2") (pinfunction "C_2") (pintype "passive"))
      (node (ref "D18") (pin "2") (pinfunction "C_2") (pintype "passive"))
      (node (ref "D19") (pin "2") (pinfunction "C_2") (pintype "passive"))
      (node (ref "D20") (pin "2") (pinfunction "C_2") (pintype "passive"))
      (node (ref "D21") (pin "2") (pinfunction "C_2") (pintype "passive"))
      (node (ref "D22") (pin "2") (pinfunction "C_2") (pintype "passive"))
      (node (ref "D23") (pin "2") (pinfunction "C_2") (pintype "passive"))
      (node (ref "D24") (pin "2") (pinfunction "C_2") (pintype "passive"))
      (node (ref "D25") (pin "2") (pinfunction "C_2") (pintype "passive"))
      (node (ref "D26") (pin "2") (pinfunction "C_2") (pintype "passive"))
      (node (ref "D27") (pin "2") (pinfunction "C_2") (pintype "passive"))
      (node (ref "D28") (pin "2") (pinfunction "C_2") (pintype "passive"))
      (node (ref "D29") (pin "2") (pinfunction "C_2") (pintype "passive"))
      (node (ref "K12") (pin "1") (pinfunction "+_1") (pintype "passive"))
      (node (ref "K13") (pin "1") (pinfunction "+_1") (pintype "passive"))
      (node (ref "K14") (pin "1") (pinfunction "+_1") (pintype "passive"))
      (node (ref "K15") (pin "1") (pinfunction "+_1") (pintype "passive"))
      (node (ref "K16") (pin "1") (pinfunction "+_1") (pintype "passive"))
      (node (ref "K17") (pin "1") (pinfunction "+_1") (pintype "passive"))
      (node (ref "K18") (pin "1") (pinfunction "+_1") (pintype "passive"))
      (node (ref "K19") (pin "1") (pinfunction "+_1") (pintype "passive"))
      (node (ref "K20") (pin "1") (pinfunction "+_1") (pintype "passive"))
      (node (ref "K21") (pin "1") (pinfunction "+_1") (pintype "passive"))
      (node (ref "K22") (pin "1") (pinfunction "+_1") (pintype "passive"))
      (node (ref "K23") (pin "1") (pinfunction "+_1") (pintype "passive"))
      (node (ref "K24") (pin "1") (pinfunction "+_1") (pintype "passive"))
      (node (ref "K25") (pin "1") (pinfunction "+_1") (pintype "passive"))
      (node (ref "K26") (pin "1") (pinfunction "+_1") (pintype "passive"))
      (node (ref "K27") (pin "1") (pinfunction "+_1") (pintype "passive"))
    )
    (net (code "106") (name "GND") (class "Default")
      (node (ref "Q11") (pin "2") (pinfunction "S_2") (pintype "passive"))
      (node (ref "Q12") (pin "2") (pinfunction "S_2") (pintype "passive"))
      (node (ref "Q13") (pin "2") (pinfunction "S_2") (pintype "passive"))
      (node (ref "Q14") (pin "2") (pinfunction "S_2") (pintype "passive"))
      (node (ref "Q15") (pin "2") (pinfunction "S_2") (pintype "passive"))
      (node (ref "Q16") (pin "2") (pinfunction "S_2") (pintype "passive"))
      (node (ref "Q17") (pin "2") (pinfunction "S_2") (pintype "passive"))
      (node (ref "Q18") (pin "2") (pinfunction "S_2") (pintype "passive"))
      (node (ref "Q19") (pin "2") (pinfunction "S_2") (pintype "passive"))
      (node (ref "Q20") (pin "2") (pinfunction "S_2") (pintype "passive"))
      (node (ref "Q21") (pin "2") (pinfunction "S_2") (pintype "passive"))
      (node (ref "Q22") (pin "2") (pinfunction "S_2") (pintype "passive"))
      (node (ref "Q23") (pin "2") (pinfunction "S_2") (pintype "passive"))
      (node (ref "Q24") (pin "2") (pinfunction "S_2") (pintype "passive"))
      (node (ref "Q25") (pin "2") (pinfunction "S_2") (pintype "passive"))
      (node (ref "Q26") (pin "2") (pinfunction "S_2") (pintype "passive"))
      (node (ref "R16") (pin "1") (pinfunction "1_1") (pintype "passive"))
      (node (ref "R17") (pin "1") (pinfunction "1_1") (pintype "passive"))
      (node (ref "R18") (pin "1") (pinfunction "1_1") (pintype "passive"))
      (node (ref "R19") (pin "1") (pinfunction "1_1") (pintype "passive"))
      (node (ref "R20") (pin "1") (pinfunction "1_1") (pintype "passive"))
      (node (ref "R21") (pin "1") (pinfunction "1_1") (pintype "passive"))
      (node (ref "R22") (pin "1") (pinfunction "1_1") (pintype "passive"))
      (node (ref "R23") (pin "1") (pinfunction "1_1") (pintype "passive"))
      (node (ref "R24") (pin "1") (pinfunction "1_1") (pintype "passive"))
      (node (ref "R25") (pin "1") (pinfunction "1_1") (pintype "passive"))
      (node (ref "R26") (pin "1") (pinfunction "1_1") (pintype "passive"))
      (node (ref "R27") (pin "1") (pinfunction "1_1") (pintype "passive"))
      (node (ref "R28") (pin "1") (pinfunction "1_1") (pintype "passive"))
      (node (ref "R29") (pin "1") (pinfunction "1_1") (pintype "passive"))
      (node (ref "R30") (pin "1") (pinfunction "1_1") (pintype "passive"))
      (node (ref "R31") (pin "1") (pinfunction "1_1") (pintype "passive"))
    )
    (net (code "107") (name "Net-(D14-A)") (class "Default")
      (node (ref "D14") (pin "1") (pinfunction "A_1") (pintype "passive"))
      (node (ref "K12") (pin "5") (pinfunction "-_5") (pintype "passive"))
      (node (ref "Q12") (pin "3") (pinfunction "D_3") (pintype "passive"))
    )
    (net (code "108") (name "Net-(D15-A)") (class "Default")
      (node (ref "D15") (pin "1") (pinfunction "A_1") (pintype "passive"))
      (node (ref "K13") (pin "5") (pinfunction "-_5") (pintype "passive"))
      (node (ref "Q13") (pin "3") (pinfunction "D_3") (pintype "passive"))
    )
    (net (code "109") (name "Net-(D16-A)") (class "Default")
      (node (ref "D16") (pin "1") (pinfunction "A_1") (pintype "passive"))
      (node (ref "K14") (pin "5") (pinfunction "-_5") (pintype "passive"))
      (node (ref "Q14") (pin "3") (pinfunction "D_3") (pintype "passive"))
    )
    (net (code "110") (name "Net-(D17-A)") (class "Default")
      (node (ref "D17") (pin "1") (pinfunction "A_1") (pintype "passive"))
      (node (ref "K15") (pin "5") (pinfunction "-_5") (pintype "passive"))
      (node (ref "Q15") (pin "3") (pinfunction "D_3") (pintype "passive"))
    )
    (net (code "111") (name "Net-(D18-A)") (class "Default")
      (node (ref "D18") (pin "1") (pinfunction "A_1") (pintype "passive"))
      (node (ref "K16") (pin "5") (pinfunction "-_5") (pintype "passive"))
      (node (ref "Q16") (pin "3") (pinfunction "D_3") (pintype "passive"))
    )
    (net (code "112") (name "Net-(D19-A)") (class "Default")
      (node (ref "D19") (pin "1") (pinfunction "A_1") (pintype "passive"))
      (node (ref "K17") (pin "5") (pinfunction "-_5") (pintype "passive"))
      (node (ref "Q17") (pin "3") (pinfunction "D_3") (pintype "passive"))
    )
    (net (code "113") (name "Net-(D20-A)") (class "Default")
      (node (ref "D20") (pin "1") (pinfunction "A_1") (pintype "passive"))
      (node (ref "K18") (pin "5") (pinfunction "-_5") (pintype "passive"))
      (node (ref "Q18") (pin "3") (pinfunction "D_3") (pintype "passive"))
    )
    (net (code "114") (name "Net-(D21-A)") (class "Default")
      (node (ref "D21") (pin "1") (pinfunction "A_1") (pintype "passive"))
      (node (ref "K19") (pin "5") (pinfunction "-_5") (pintype "passive"))
      (node (ref "Q19") (pin "3") (pinfunction "D_3") (pintype "passive"))
    )
    (net (code "115") (name "Net-(D22-A)") (class "Default")
      (node (ref "D22") (pin "1") (pinfunction "A_1") (pintype "passive"))
      (node (ref "K20") (pin "5") (pinfunction "-_5") (pintype "passive"))
      (node (ref "Q20") (pin "3") (pinfunction "D_3") (pintype "passive"))
    )
    (net (code "116") (name "Net-(D23-A)") (class "Default")
      (node (ref "D23") (pin "1") (pinfunction "A_1") (pintype "passive"))
      (node (ref "K21") (pin "5") (pinfunction "-_5") (pintype "passive"))
      (node (ref "Q21") (pin "3") (pinfunction "D_3") (pintype "passive"))
    )
    (net (code "117") (name "Net-(D24-A)") (class "Default")
      (node (ref "D24") (pin "1") (pinfunction "A_1") (pintype "passive"))
      (node (ref "K22") (pin "5") (pinfunction "-_5") (pintype "passive"))
      (node (ref "Q22") (pin "3") (pinfunction "D_3") (pintype "passive"))
    )
    (net (code "118") (name "Net-(D25-A)") (class "Default")
      (node (ref "D25") (pin "1") (pinfunction "A_1") (pintype "passive"))
      (node (ref "K23") (pin "5") (pinfunction "-_5") (pintype "passive"))
      (node (ref "Q23") (pin "3") (pinfunction "D_3") (pintype "passive"))
    )
    (net (code "119") (name "Net-(D26-A)") (class "Default")
      (node (ref "D26") (pin "1") (pinfunction "A_1") (pintype "passive"))
      (node (ref "K24") (pin "5") (pinfunction "-_5") (pintype "passive"))
      (node (ref "Q24") (pin "3") (pinfunction "D_3") (pintype "passive"))
    )
    (net (code "120") (name "Net-(D27-A)") (class "Default")
      (node (ref "D27") (pin "1") (pinfunction "A_1") (pintype "passive"))
      (node (ref "K25") (pin "5") (pinfunction "-_5") (pintype "passive"))
      (node (ref "Q25") (pin "3") (pinfunction "D_3") (pintype "passive"))
    )
    (net (code "121") (name "Net-(D28-A)") (class "Default")
      (node (ref "D28") (pin "1") (pinfunction "A_1") (pintype "passive"))
      (node (ref "K26") (pin "5") (pinfunction "-_5") (pintype "passive"))
      (node (ref "Q26") (pin "3") (pinfunction "D_3") (pintype "passive"))
    )
    (net (code "122") (name "Net-(D29-A)") (class "Default")
      (node (ref "D29") (pin "1") (pinfunction "A_1") (pintype "passive"))
      (node (ref "K27") (pin "5") (pinfunction "-_5") (pintype "passive"))
      (node (ref "Q11") (pin "3") (pinfunction "D_3") (pintype "passive"))
    )
    (net (code "123") (name "Net-(K12A-Cin)") (class "Default")
      (node (ref "K12") (pin "2") (pinfunction "Cin_2") (pintype "passive"))
      (node (ref "X6") (pin "1") (pinfunction "+_1") (pintype "passive"))
    )
    (net (code "124") (name "Net-(K12A-Cno)") (class "Default")
      (node (ref "K12") (pin "3") (pinfunction "Cno_3") (pintype "passive"))
      (node (ref "X5") (pin "2") (pinfunction "2_2") (pintype "passive"))
    )
    (net (code "125") (name "Net-(K13A-Cin)") (class "Default")
      (node (ref "K13") (pin "2") (pinfunction "Cin_2") (pintype "passive"))
      (node (ref "X6") (pin "2") (pinfunction "-_2") (pintype "passive"))
    )
    (net (code "126") (name "Net-(K13A-Cno)") (class "Default")
      (node (ref "K13") (pin "3") (pinfunction "Cno_3") (pintype "passive"))
      (node (ref "X5") (pin "1") (pinfunction "1_1") (pintype "passive"))
    )
    (net (code "127") (name "Net-(K14A-Cin)") (class "Default")
      (node (ref "K14") (pin "2") (pinfunction "Cin_2") (pintype "passive"))
      (node (ref "X9") (pin "1") (pinfunction "+_1") (pintype "passive"))
    )
    (net (code "128") (name "Net-(K14A-Cno)") (class "Default")
      (node (ref "K14") (pin "3") (pinfunction "Cno_3") (pintype "passive"))
      (node (ref "X8") (pin "2") (pinfunction "2_2") (pintype "passive"))
    )
    (net (code "129") (name "Net-(K15A-Cin)") (class "Default")
      (node (ref "K15") (pin "2") (pinfunction "Cin_2") (pintype "passive"))
      (node (ref "X9") (pin "2") (pinfunction "-_2") (pintype "passive"))
    )
    (net (code "130") (name "Net-(K15A-Cno)") (class "Default")
      (node (ref "K15") (pin "3") (pinfunction "Cno_3") (pintype "passive"))
      (node (ref "X8") (pin "1") (pinfunction "1_1") (pintype "passive"))
    )
    (net (code "131") (name "Net-(K16A-Cin)") (class "Default")
      (node (ref "K16") (pin "2") (pinfunction "Cin_2") (pintype "passive"))
      (node (ref "X12") (pin "1") (pinfunction "+_1") (pintype "passive"))
    )
    (net (code "132") (name "Net-(K16A-Cno)") (class "Default")
      (node (ref "K16") (pin "3") (pinfunction "Cno_3") (pintype "passive"))
      (node (ref "X11") (pin "2") (pinfunction "2_2") (pintype "passive"))
    )
    (net (code "133") (name "Net-(K17A-Cin)") (class "Default")
      (node (ref "K17") (pin "2") (pinfunction "Cin_2") (pintype "passive"))
      (node (ref "X12") (pin "2") (pinfunction "-_2") (pintype "passive"))
    )
    (net (code "134") (name "Net-(K17A-Cno)") (class "Default")
      (node (ref "K17") (pin "3") (pinfunction "Cno_3") (pintype "passive"))
      (node (ref "X11") (pin "1") (pinfunction "1_1") (pintype "passive"))
    )
    (net (code "135") (name "Net-(K18A-Cin)") (class "Default")
      (node (ref "K18") (pin "2") (pinfunction "Cin_2") (pintype "passive"))
      (node (ref "X13") (pin "1") (pinfunction "+_1") (pintype "passive"))
    )
    (net (code "136") (name "Net-(K18A-Cno)") (class "Default")
      (node (ref "K18") (pin "3") (pinfunction "Cno_3") (pintype "passive"))
      (node (ref "X14") (pin "2") (pinfunction "2_2") (pintype "passive"))
    )
    (net (code "137") (name "Net-(K19A-Cin)") (class "Default")
      (node (ref "K19") (pin "2") (pinfunction "Cin_2") (pintype "passive"))
      (node (ref "X13") (pin "2") (pinfunction "-_2") (pintype "passive"))
    )
    (net (code "138") (name "Net-(K19A-Cno)") (class "Default")
      (node (ref "K19") (pin "3") (pinfunction "Cno_3") (pintype "passive"))
      (node (ref "X14") (pin "1") (pinfunction "1_1") (pintype "passive"))
    )
    (net (code "139") (name "Net-(K20A-Cin)") (class "Default")
      (node (ref "K20") (pin "2") (pinfunction "Cin_2") (pintype "passive"))
      (node (ref "X16") (pin "1") (pinfunction "+_1") (pintype "passive"))
    )
    (net (code "140") (name "Net-(K20A-Cno)") (class "Default")
      (node (ref "K20") (pin "3") (pinfunction "Cno_3") (pintype "passive"))
      (node (ref "X18") (pin "2") (pinfunction "2_2") (pintype "passive"))
    )
    (net (code "141") (name "Net-(K21A-Cin)") (class "Default")
      (node (ref "K21") (pin "2") (pinfunction "Cin_2") (pintype "passive"))
      (node (ref "X16") (pin "2") (pinfunction "-_2") (pintype "passive"))
    )
    (net (code "142") (name "Net-(K21A-Cno)") (class "Default")
      (node (ref "K21") (pin "3") (pinfunction "Cno_3") (pintype "passive"))
      (node (ref "X18") (pin "1") (pinfunction "1_1") (pintype "passive"))
    )
    (net (code "143") (name "Net-(K22A-Cin)") (class "Default")
      (node (ref "K22") (pin "2") (pinfunction "Cin_2") (pintype "passive"))
      (node (ref "X19") (pin "1") (pinfunction "+_1") (pintype "passive"))
    )
    (net (code "144") (name "Net-(K22A-Cno)") (class "Default")
      (node (ref "K22") (pin "3") (pinfunction "Cno_3") (pintype "passive"))
      (node (ref "X20") (pin "2") (pinfunction "2_2") (pintype "passive"))
    )
    (net (code "145") (name "Net-(K23A-Cin)") (class "Default")
      (node (ref "K23") (pin "2") (pinfunction "Cin_2") (pintype "passive"))
      (node (ref "X19") (pin "2") (pinfunction "-_2") (pintype "passive"))
    )
    (net (code "146") (name "Net-(K23A-Cno)") (class "Default")
      (node (ref "K23") (pin "3") (pinfunction "Cno_3") (pintype "passive"))
      (node (ref "X20") (pin "1") (pinfunction "1_1") (pintype "passive"))
    )
    (net (code "147") (name "Net-(K24A-Cin)") (class "Default")
      (node (ref "K24") (pin "2") (pinfunction "Cin_2") (pintype "passive"))
      (node (ref "X22") (pin "1") (pinfunction "+_1") (pintype "passive"))
    )
    (net (code "148") (name "Net-(K24A-Cno)") (class "Default")
      (node (ref "K24") (pin "3") (pinfunction "Cno_3") (pintype "passive"))
      (node (ref "X23") (pin "2") (pinfunction "2_2") (pintype "passive"))
    )
    (net (code "149") (name "Net-(K25A-Cin)") (class "Default")
      (node (ref "K25") (pin "2") (pinfunction "Cin_2") (pintype "passive"))
      (node (ref "X22") (pin "2") (pinfunction "-_2") (pintype "passive"))
    )
    (net (code "150") (name "Net-(K25A-Cno)") (class "Default")
      (node (ref "K25") (pin "3") (pinfunction "Cno_3") (pintype "passive"))
      (node (ref "X23") (pin "1") (pinfunction "1_1") (pintype "passive"))
    )
    (net (code "151") (name "Net-(K26A-Cin)") (class "Default")
      (node (ref "K26") (pin "2") (pinfunction "Cin_2") (pintype "passive"))
      (node (ref "X24") (pin "1") (pinfunction "+_1") (pintype "passive"))
    )
    (net (code "152") (name "Net-(K26A-Cno)") (class "Default")
      (node (ref "K26") (pin "3") (pinfunction "Cno_3") (pintype "passive"))
      (node (ref "X26") (pin "2") (pinfunction "2_2") (pintype "passive"))
    )
    (net (code "153") (name "Net-(K27A-Cin)") (class "Default")
      (node (ref "K27") (pin "2") (pinfunction "Cin_2") (pintype "passive"))
      (node (ref "X24") (pin "2") (pinfunction "-_2") (pintype "passive"))
    )
    (net (code "154") (name "Net-(K27A-Cno)") (class "Default")
      (node (ref "K27") (pin "3") (pinfunction "Cno_3") (pintype "passive"))
      (node (ref "X26") (pin "1") (pinfunction "1_1") (pintype "passive"))
    )
    (net (code "155") (name "unconnected-(K12A-Cnc-Pad4)") (class "Default")
      (node (ref "K12") (pin "4") (pinfunction "Cnc_4") (pintype "passive+no_connect"))
    )
    (net (code "156") (name "unconnected-(K13A-Cnc-Pad4)") (class "Default")
      (node (ref "K13") (pin "4") (pinfunction "Cnc_4") (pintype "passive+no_connect"))
    )
    (net (code "157") (name "unconnected-(K14A-Cnc-Pad4)") (class "Default")
      (node (ref "K14") (pin "4") (pinfunction "Cnc_4") (pintype "passive+no_connect"))
    )
    (net (code "158") (name "unconnected-(K15A-Cnc-Pad4)") (class "Default")
      (node (ref "K15") (pin "4") (pinfunction "Cnc_4") (pintype "passive+no_connect"))
    )
    (net (code "159") (name "unconnected-(K16A-Cnc-Pad4)") (class "Default")
      (node (ref "K16") (pin "4") (pinfunction "Cnc_4") (pintype "passive+no_connect"))
    )
    (net (code "160") (name "unconnected-(K17A-Cnc-Pad4)") (class "Default")
      (node (ref "K17") (pin "4") (pinfunction "Cnc_4") (pintype "passive+no_connect"))
    )
    (net (code "161") (name "unconnected-(K18A-Cnc-Pad4)") (class "Default")
      (node (ref "K18") (pin "4") (pinfunction "Cnc_4") (pintype "passive+no_connect"))
    )
    (net (code "162") (name "unconnected-(K19A-Cnc-Pad4)") (class "Default")
      (node (ref "K19") (pin "4") (pinfunction "Cnc_4") (pintype "passive+no_connect"))
    )
    (net (code "163") (name "unconnected-(K20A-Cnc-Pad4)") (class "Default")
      (node (ref "K20") (pin "4") (pinfunction "Cnc_4") (pintype "passive+no_connect"))
    )
    (net (code "164") (name "unconnected-(K21A-Cnc-Pad4)") (class "Default")
      (node (ref "K21") (pin "4") (pinfunction "Cnc_4") (pintype "passive+no_connect"))
    )
    (net (code "165") (name "unconnected-(K22A-Cnc-Pad4)") (class "Default")
      (node (ref "K22") (pin "4") (pinfunction "Cnc_4") (pintype "passive+no_connect"))
    )
    (net (code "166") (name "unconnected-(K23A-Cnc-Pad4)") (class "Default")
      (node (ref "K23") (pin "4") (pinfunction "Cnc_4") (pintype "passive+no_connect"))
    )
    (net (code "167") (name "unconnected-(K24A-Cnc-Pad4)") (class "Default")
      (node (ref "K24") (pin "4") (pinfunction "Cnc_4") (pintype "passive+no_connect"))
    )
    (net (code "168") (name "unconnected-(K25A-Cnc-Pad4)") (class "Default")
      (node (ref "K25") (pin "4") (pinfunction "Cnc_4") (pintype "passive+no_connect"))
    )
    (net (code "169") (name "unconnected-(K26A-Cnc-Pad4)") (class "Default")
      (node (ref "K26") (pin "4") (pinfunction "Cnc_4") (pintype "passive+no_connect"))
    )
    (net (code "170") (name "unconnected-(K27A-Cnc-Pad4)") (class "Default")
      (node (ref "K27") (pin "4") (pinfunction "Cnc_4") (pintype "passive+no_connect"))
    )
  )
)
